# MCORD_AFE_SEC.net
KiCad netlist of a schematic drawn in Altium Designer
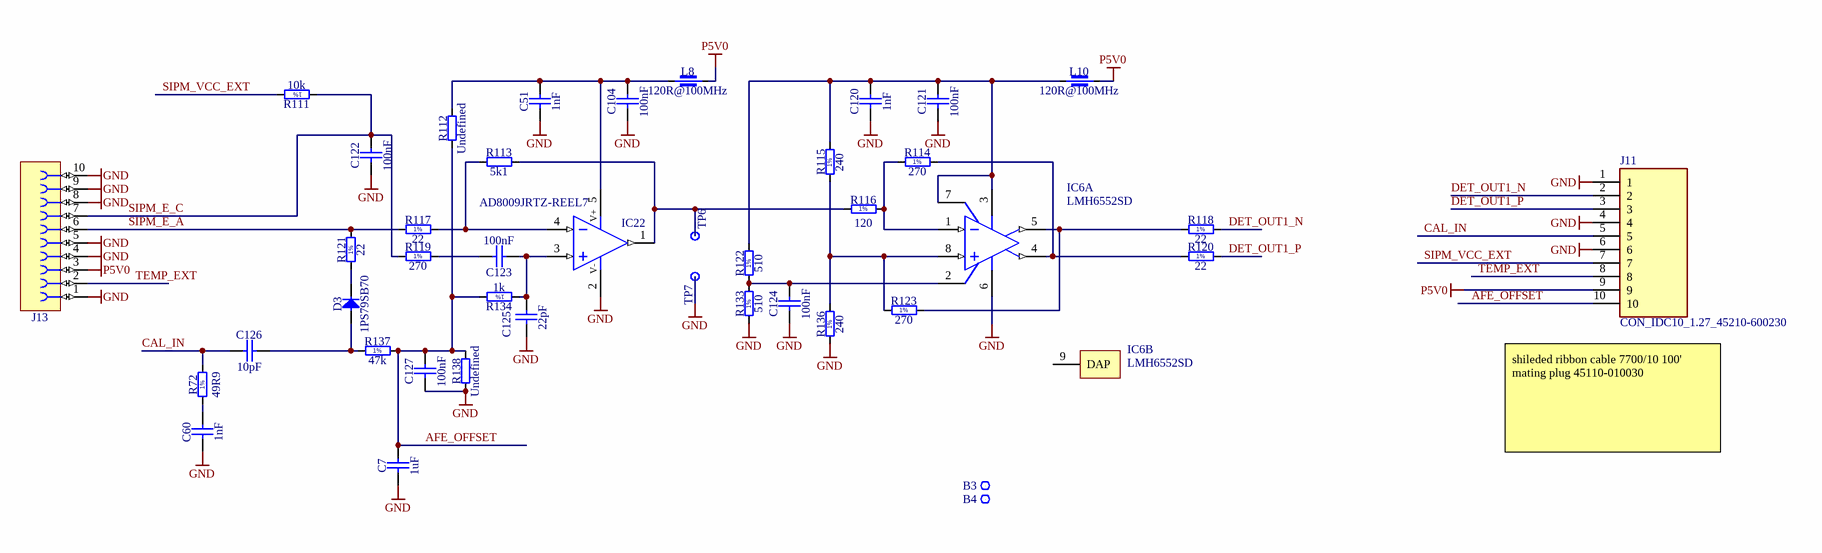
[diagram p0: MCORD_AFE_SEC.SchDoc]

(export (version "E")
  (design (tool "Eeschema 10.0.6"))
  (components
    (comp (ref "B3")
      (value "Plated Hole")
      (footprint "MTG320_550")
      (description "Single Terminal Socket")
      (fields (field (name "PART NUMBER") "PLATED_HOLE3.2_PAD5.5") (field (name "AUTHOR") "CERN DEM JMW"))
      (libsource (lib "Eletro-mechanical") (part "Single Terminal Socket"))
    )
    (comp (ref "B4")
      (value "Plated Hole")
      (footprint "MTG320_550")
      (description "Single Terminal Socket")
      (fields (field (name "PART NUMBER") "PLATED_HOLE3.2_PAD5.5") (field (name "AUTHOR") "CERN DEM JMW"))
      (libsource (lib "Eletro-mechanical") (part "Single Terminal Socket"))
    )
    (comp (ref "C7")
      (value "1uF")
      (footprint "CAPC1608X87N")
      (description "Non-polarised capacitor")
      (fields
        (field (name "PART NUMBER") "CC0603_1UF_16V_10%_X7R")
        (field (name "VOLTAGE") "16V")
        (field (name "AUTHOR") "CERN DEM JLC")
      )
      (libsource (lib "Capacitors") (part "Capacitor - non polarized"))
    )
    (comp (ref "C51")
      (value "1nF")
      (footprint "CAPC1005X55N")
      (description "Non-polarised capacitor")
      (fields
        (field (name "PART NUMBER") "CC0402_1NF_50V_5%_C0G")
        (field (name "VOLTAGE") "50V")
        (field (name "AUTHOR") "CERN DEM BC")
      )
      (libsource (lib "Capacitors") (part "Capacitor - non polarized"))
    )
    (comp (ref "C60")
      (value "1nF")
      (footprint "CAPC1005X55N")
      (description "Non-polarised capacitor")
      (fields
        (field (name "PART NUMBER") "CC0402_1NF_50V_5%_C0G")
        (field (name "VOLTAGE") "50V")
        (field (name "AUTHOR") "CERN DEM BC")
      )
      (libsource (lib "Capacitors") (part "Capacitor - non polarized"))
    )
    (comp (ref "C104")
      (value "100nF")
      (footprint "CAPC1005X55N")
      (description "Non-polarised capacitor")
      (fields
        (field (name "PART NUMBER") "CC0402_100NF_16V_10%_X7R")
        (field (name "VOLTAGE") "16V")
        (field (name "AUTHOR") "CERN DEM JLC")
      )
      (libsource (lib "Capacitors") (part "Capacitor - non polarized"))
    )
    (comp (ref "C120")
      (value "1nF")
      (footprint "CAPC1005X55N")
      (description "Non-polarised capacitor")
      (fields
        (field (name "PART NUMBER") "CC0402_1NF_50V_5%_C0G")
        (field (name "VOLTAGE") "50V")
        (field (name "AUTHOR") "CERN DEM BC")
      )
      (libsource (lib "Capacitors") (part "Capacitor - non polarized"))
    )
    (comp (ref "C121")
      (value "100nF")
      (footprint "CAPC1005X55N")
      (description "Non-polarised capacitor")
      (fields
        (field (name "PART NUMBER") "CC0402_100NF_16V_10%_X7R")
        (field (name "VOLTAGE") "16V")
        (field (name "AUTHOR") "CERN DEM JLC")
      )
      (libsource (lib "Capacitors") (part "Capacitor - non polarized"))
    )
    (comp (ref "C122")
      (value "100nF")
      (footprint "CAPC1608X90N")
      (description "Non-polarised capacitor")
      (fields
        (field (name "PART NUMBER") "CC0603_100NF_100V_10%_X7R")
        (field (name "VOLTAGE") "100V")
        (field (name "AUTHOR") "CERN DEM JLC")
      )
      (libsource (lib "Capacitors") (part "Capacitor - non polarized"))
    )
    (comp (ref "C123")
      (value "100nF")
      (footprint "CAPC1608X90N")
      (description "Non-polarised capacitor")
      (fields
        (field (name "PART NUMBER") "CC0603_100NF_100V_10%_X7R")
        (field (name "VOLTAGE") "100V")
        (field (name "AUTHOR") "CERN DEM JLC")
      )
      (libsource (lib "Capacitors") (part "Capacitor - non polarized"))
    )
    (comp (ref "C124")
      (value "100nF")
      (footprint "CAPC1005X55N")
      (description "Non-polarised capacitor")
      (fields
        (field (name "PART NUMBER") "CC0402_100NF_16V_10%_X7R")
        (field (name "VOLTAGE") "16V")
        (field (name "AUTHOR") "CERN DEM JLC")
      )
      (libsource (lib "Capacitors") (part "Capacitor - non polarized"))
    )
    (comp (ref "C125")
      (value "22pF")
      (footprint "CAPC1005X55N")
      (description "Non-polarised capacitor")
      (fields
        (field (name "PART NUMBER") "CC0402_22PF_50V_5%_C0G")
        (field (name "VOLTAGE") "50V")
        (field (name "AUTHOR") "CERN DEM JLC")
      )
      (libsource (lib "Capacitors") (part "Capacitor - non polarized"))
    )
    (comp (ref "C126")
      (value "10pF")
      (footprint "CAPC1608X87N")
      (description "Non-polarised capacitor")
      (fields
        (field (name "PART NUMBER") "CC0603_10PF_50V_5%_NP0")
        (field (name "VOLTAGE") "50V")
        (field (name "AUTHOR") "CERN DEM JLC")
      )
      (libsource (lib "Capacitors") (part "Capacitor - non polarized"))
    )
    (comp (ref "C127")
      (value "100nF")
      (footprint "CAPC1005X55N")
      (description "Non-polarised capacitor")
      (fields
        (field (name "PART NUMBER") "CC0402_100NF_16V_10%_X7R")
        (field (name "VOLTAGE") "16V")
        (field (name "AUTHOR") "CERN DEM JLC")
      )
      (libsource (lib "Capacitors") (part "Capacitor - non polarized"))
    )
    (comp (ref "D3")
      (value "1PS79SB70")
      (footprint "SODFL1608X65N")
      (description "Diode")
      (fields (field (name "VOLTAGE") "70V") (field (name "POWER") "70mA") (field (name "AUTHOR") "GK"))
      (libsource (lib "Diodes") (part "D_1PS79SB70"))
    )
    (comp (ref "IC6")
      (value "LMH6552SD")
      (footprint "SDA08C")
      (description "1.5 GHz Fully Differential Amplifier, 8-pin LLP")
      (fields (field (name "MANUFACTURER") "National Semiconductor"))
      (libsource (lib "Altium Content Vault") (part "AMP-DIFA-LMH6552-9"))
    )
    (comp (ref "IC22")
      (value "AD8009JRTZ-REEL7")
      (footprint "SOT95P280X145-5N")
      (description "Operational Amplifier")
      (fields (field (name "MANUFACTURER") "ANALOG DEVICES") (field (name "AUTHOR") "CERN DEM JLC"))
      (libsource (lib "ICs And Semiconductors") (part "Operational Amplifier Type7"))
    )
    (comp (ref "J11")
      (value "CON_IDC10_1.27_45210-600230")
      (footprint "SamacSys:SHDR10W38P127_2X5_1069X594X747P")
      (description "Connector")
      (fields
        (field (name "MANUFACTURER_PART_NUMBER") "45210-600230")
        (field (name "MOUSER PART NUMBER") "517-45210-600230")
      )
      (libsource (lib "LIBRARY_SCH") (part "CON_IDC10_1.27_45210-600230"))
    )
    (comp (ref "J13")
      (value "FFC/FPC")
      (footprint "MOLEX_52745-1097")
      (description "Connector 10 Female")
      (fields
        (field (name "PART NUMBER") "MOLEX_52745-1097")
        (field (name "MANUFACTURER") "MOLEX")
        (field (name "AUTHOR") "CERN DEM JLC")
      )
      (libsource (lib "Connectors") (part "Connector 10 Female"))
    )
    (comp (ref "L8")
      (value "120R@100MHz")
      (footprint "INDC1005X55N")
      (fields
        (field (name "PART NUMBER") "IND0402_MURATA_BLM15PX121SN1D")
        (field (name "POWER") "2A")
        (field (name "TOLERANCE") "±25%")
        (field (name "AUTHOR") "CERN DEM JMW")
      )
      (libsource (lib "Inductors & Transformers") (part "Ferrite Bead"))
    )
    (comp (ref "L10")
      (value "120R@100MHz")
      (footprint "INDC1005X55N")
      (fields
        (field (name "PART NUMBER") "IND0402_MURATA_BLM15PX121SN1D")
        (field (name "POWER") "2A")
        (field (name "TOLERANCE") "±25%")
        (field (name "AUTHOR") "CERN DEM JMW")
      )
      (libsource (lib "Inductors & Transformers") (part "Ferrite Bead"))
    )
    (comp (ref "R72")
      (value "49R9")
      (footprint "RESC1005X40N")
      (description "Resistor - 1%")
      (fields
        (field (name "PART NUMBER") "R0402_49R9_1%_0.0625W_100PPM")
        (field (name "POWER") "0.0625W")
        (field (name "AUTHOR") "CERN DEM JLC")
      )
      (libsource (lib "Resistors") (part "Resistor - 1%"))
    )
    (comp (ref "R111")
      (value "10k")
      (footprint "RESC1005X40N")
      (description "Resistor - 1%")
      (fields
        (field (name "PART NUMBER") "R0402_10K_1%_0.0625W_100PPM")
        (field (name "POWER") "0.0625W")
        (field (name "AUTHOR") "CERN DEM JLC")
      )
      (libsource (lib "Resistors") (part "Resistor - 1%"))
    )
    (comp (ref "R112")
      (value "Undefined")
      (footprint "RESC1005X40N")
      (description "Resistor")
      (fields (field (name "PART NUMBER") "R0402_NO-VALUE") (field (name "AUTHOR") "CERN DEM JLC"))
      (libsource (lib "Resistors") (part "Resistor"))
    )
    (comp (ref "R113")
      (value "5k1")
      (footprint "RESC1005X40N")
      (description "Resistor - 1%")
      (fields
        (field (name "PART NUMBER") "R0402_5K1_1%_0.0625W_100PPM")
        (field (name "POWER") "0.0625W")
        (field (name "AUTHOR") "CERN DEM JLC")
      )
      (libsource (lib "Resistors") (part "Resistor - 1%"))
    )
    (comp (ref "R114")
      (value "270")
      (footprint "RESC1005X40N")
      (description "Resistor - 1%")
      (fields
        (field (name "PART NUMBER") "R0402_270R_1%_0.0625W_100PPM")
        (field (name "POWER") "0.0625W")
        (field (name "AUTHOR") "CERN DEM JLC")
      )
      (libsource (lib "Resistors") (part "Resistor - 1%"))
    )
    (comp (ref "R115")
      (value "240")
      (footprint "RESC1005X40N")
      (description "Resistor - 1%")
      (fields
        (field (name "PART NUMBER") "R0402_240R_1%_0.0625W_100PPM")
        (field (name "POWER") "0.0625W")
        (field (name "AUTHOR") "CERN DEM JLC")
      )
      (libsource (lib "Resistors") (part "Resistor - 1%"))
    )
    (comp (ref "R116")
      (value "120")
      (footprint "RESC1005X40N")
      (description "Resistor - 1%")
      (fields
        (field (name "PART NUMBER") "R0402_120R_1%_0.0625W_100PPM")
        (field (name "POWER") "0.0625W")
        (field (name "AUTHOR") "CERN DEM JLC")
      )
      (libsource (lib "Resistors") (part "Resistor - 1%"))
    )
    (comp (ref "R117")
      (value "22")
      (footprint "RESC1608X55N")
      (description "Resistor - 1%")
      (fields
        (field (name "PART NUMBER") "R0603_22R_1%_0.1W_100PPM")
        (field (name "POWER") "0.1W")
        (field (name "AUTHOR") "CERN DEM JLC")
      )
      (libsource (lib "") (part "Resistor - 1%_1"))
    )
    (comp (ref "R118")
      (value "22")
      (footprint "RESC1608X55N")
      (description "Resistor - 1%")
      (fields
        (field (name "PART NUMBER") "R0603_22R_1%_0.1W_100PPM")
        (field (name "POWER") "0.1W")
        (field (name "AUTHOR") "CERN DEM JLC")
      )
      (libsource (lib "") (part "Resistor - 1%_1"))
    )
    (comp (ref "R119")
      (value "270")
      (footprint "RESC1005X40N")
      (description "Resistor - 1%")
      (fields
        (field (name "PART NUMBER") "R0402_270R_1%_0.0625W_100PPM")
        (field (name "POWER") "0.0625W")
        (field (name "AUTHOR") "CERN DEM JLC")
      )
      (libsource (lib "Resistors") (part "Resistor - 1%"))
    )
    (comp (ref "R120")
      (value "22")
      (footprint "RESC1608X55N")
      (description "Resistor - 1%")
      (fields
        (field (name "PART NUMBER") "R0603_22R_1%_0.1W_100PPM")
        (field (name "POWER") "0.1W")
        (field (name "AUTHOR") "CERN DEM JLC")
      )
      (libsource (lib "") (part "Resistor - 1%_1"))
    )
    (comp (ref "R121")
      (value "22")
      (footprint "RESC1608X55N")
      (description "Resistor - 1%")
      (fields
        (field (name "PART NUMBER") "R0603_22R_1%_0.1W_100PPM")
        (field (name "POWER") "0.1W")
        (field (name "AUTHOR") "CERN DEM JLC")
      )
      (libsource (lib "") (part "Resistor - 1%_1"))
    )
    (comp (ref "R122")
      (value "510")
      (footprint "RESC1005X40N")
      (description "Resistor - 1%")
      (fields
        (field (name "PART NUMBER") "R0402_510R_1%_0.0625W_100PPM")
        (field (name "POWER") "0.0625W")
        (field (name "AUTHOR") "CERN DEM JLC")
      )
      (libsource (lib "Resistors") (part "Resistor - 1%"))
    )
    (comp (ref "R123")
      (value "270")
      (footprint "RESC1005X40N")
      (description "Resistor - 1%")
      (fields
        (field (name "PART NUMBER") "R0402_270R_1%_0.0625W_100PPM")
        (field (name "POWER") "0.0625W")
        (field (name "AUTHOR") "CERN DEM JLC")
      )
      (libsource (lib "Resistors") (part "Resistor - 1%"))
    )
    (comp (ref "R133")
      (value "510")
      (footprint "RESC1005X40N")
      (description "Resistor - 1%")
      (fields
        (field (name "PART NUMBER") "R0402_510R_1%_0.0625W_100PPM")
        (field (name "POWER") "0.0625W")
        (field (name "AUTHOR") "CERN DEM JLC")
      )
      (libsource (lib "Resistors") (part "Resistor - 1%"))
    )
    (comp (ref "R134")
      (value "1k")
      (footprint "RESC1005X40N")
      (description "Resistor - 1%")
      (fields
        (field (name "PART NUMBER") "R0402_1K_1%_0.0625W_100PPM")
        (field (name "POWER") "0.0625W")
        (field (name "AUTHOR") "CERN DEM JLC")
      )
      (libsource (lib "Resistors") (part "Resistor - 1%"))
    )
    (comp (ref "R136")
      (value "240")
      (footprint "RESC1005X40N")
      (description "Resistor - 1%")
      (fields
        (field (name "PART NUMBER") "R0402_240R_1%_0.0625W_100PPM")
        (field (name "POWER") "0.0625W")
        (field (name "AUTHOR") "CERN DEM JLC")
      )
      (libsource (lib "Resistors") (part "Resistor - 1%"))
    )
    (comp (ref "R137")
      (value "47k")
      (footprint "RESC1005X40N")
      (description "Resistor - 1%")
      (fields
        (field (name "PART NUMBER") "R0402_47K_1%_0.0625W_100PPM")
        (field (name "POWER") "0.0625W")
        (field (name "AUTHOR") "CERN DEM JLC")
      )
      (libsource (lib "Resistors") (part "Resistor - 1%"))
    )
    (comp (ref "R138")
      (value "Undefined")
      (footprint "RESC1005X40N")
      (description "Resistor")
      (fields (field (name "PART NUMBER") "R0402_NO-VALUE") (field (name "AUTHOR") "CERN DEM JLC"))
      (libsource (lib "Resistors") (part "Resistor"))
    )
    (comp (ref "TP6")
      (value "Test Point")
      (footprint "TPS127")
      (fields (field (name "PART NUMBER") "SMD_PAD_1.27X1.27MM") (field (name "AUTHOR") "CERN DEM JLC"))
      (libsource (lib "Eletro-mechanical") (part "Test Point"))
    )
    (comp (ref "TP7")
      (value "Test Point")
      (footprint "TPS127")
      (fields (field (name "PART NUMBER") "SMD_PAD_1.27X1.27MM") (field (name "AUTHOR") "CERN DEM JLC"))
      (libsource (lib "Eletro-mechanical") (part "Test Point"))
    )
  )
  (nets
    (net (code "1") (name "/AFE_OFFSET") (class "Default")
      (node (ref "C127") (pin "2") (pinfunction "2_2") (pintype "passive"))
      (node (ref "C7") (pin "2") (pinfunction "2_2") (pintype "passive"))
      (node (ref "J11") (pin "10") (pinfunction "10_10") (pintype "passive"))
      (node (ref "R112") (pin "1") (pinfunction "1_1") (pintype "passive"))
      (node (ref "R134") (pin "2") (pinfunction "2_2") (pintype "passive"))
      (node (ref "R137") (pin "2") (pinfunction "2_2") (pintype "passive"))
      (node (ref "R138") (pin "2") (pinfunction "2_2") (pintype "passive"))
    )
    (net (code "2") (name "/CAL_IN") (class "Default")
      (node (ref "C126") (pin "1") (pinfunction "1_1") (pintype "passive"))
      (node (ref "J11") (pin "5") (pinfunction "5_5") (pintype "passive"))
      (node (ref "R72") (pin "2") (pinfunction "2_2") (pintype "passive"))
    )
    (net (code "3") (name "/DET_OUT1_N") (class "Default")
      (node (ref "J11") (pin "2") (pinfunction "2_2") (pintype "passive"))
      (node (ref "R118") (pin "2") (pinfunction "2_2") (pintype "passive"))
    )
    (net (code "4") (name "/DET_OUT1_P") (class "Default")
      (node (ref "J11") (pin "3") (pinfunction "3_3") (pintype "passive"))
      (node (ref "R120") (pin "2") (pinfunction "2_2") (pintype "passive"))
    )
    (net (code "5") (name "/SIPM_E_A") (class "Default")
      (node (ref "J13") (pin "6") (pinfunction "6_6") (pintype "bidirectional"))
      (node (ref "R117") (pin "1") (pinfunction "1_1") (pintype "passive"))
      (node (ref "R121") (pin "2") (pinfunction "2_2") (pintype "passive"))
    )
    (net (code "6") (name "/SIPM_E_C") (class "Default")
      (node (ref "C122") (pin "2") (pinfunction "2_2") (pintype "passive"))
      (node (ref "J13") (pin "7") (pinfunction "7_7") (pintype "bidirectional"))
      (node (ref "R111") (pin "1") (pinfunction "1_1") (pintype "passive"))
      (node (ref "R119") (pin "1") (pinfunction "1_1") (pintype "passive"))
    )
    (net (code "7") (name "/SIPM_VCC_EXT") (class "Default")
      (node (ref "J11") (pin "7") (pinfunction "7_7") (pintype "passive"))
      (node (ref "R111") (pin "2") (pinfunction "2_2") (pintype "passive"))
    )
    (net (code "8") (name "/TEMP_EXT") (class "Default")
      (node (ref "J11") (pin "8") (pinfunction "8_8") (pintype "passive"))
      (node (ref "J13") (pin "2") (pinfunction "2_2") (pintype "bidirectional"))
    )
    (net (code "9") (name "GND") (class "Default")
      (node (ref "C104") (pin "1") (pinfunction "1_1") (pintype "passive"))
      (node (ref "C120") (pin "1") (pinfunction "1_1") (pintype "passive"))
      (node (ref "C121") (pin "1") (pinfunction "1_1") (pintype "passive"))
      (node (ref "C122") (pin "1") (pinfunction "1_1") (pintype "passive"))
      (node (ref "C124") (pin "1") (pinfunction "1_1") (pintype "passive"))
      (node (ref "C125") (pin "1") (pinfunction "1_1") (pintype "passive"))
      (node (ref "C127") (pin "1") (pinfunction "1_1") (pintype "passive"))
      (node (ref "C51") (pin "1") (pinfunction "1_1") (pintype "passive"))
      (node (ref "C60") (pin "1") (pinfunction "1_1") (pintype "passive"))
      (node (ref "C7") (pin "1") (pinfunction "1_1") (pintype "passive"))
      (node (ref "IC22") (pin "2") (pinfunction "V-_2") (pintype "power_in"))
      (node (ref "IC6") (pin "6") (pinfunction "V-_6") (pintype "power_in"))
      (node (ref "J11") (pin "1") (pinfunction "1_1") (pintype "passive"))
      (node (ref "J11") (pin "4") (pinfunction "4_4") (pintype "passive"))
      (node (ref "J11") (pin "6") (pinfunction "6_6") (pintype "passive"))
      (node (ref "J13") (pin "1") (pinfunction "1_1") (pintype "bidirectional"))
      (node (ref "J13") (pin "10") (pinfunction "10_10") (pintype "bidirectional"))
      (node (ref "J13") (pin "4") (pinfunction "4_4") (pintype "bidirectional"))
      (node (ref "J13") (pin "5") (pinfunction "5_5") (pintype "bidirectional"))
      (node (ref "J13") (pin "8") (pinfunction "8_8") (pintype "bidirectional"))
      (node (ref "J13") (pin "9") (pinfunction "9_9") (pintype "bidirectional"))
      (node (ref "R133") (pin "1") (pinfunction "1_1") (pintype "passive"))
      (node (ref "R136") (pin "1") (pinfunction "1_1") (pintype "passive"))
      (node (ref "R138") (pin "1") (pinfunction "1_1") (pintype "passive"))
      (node (ref "TP7") (pin "1") (pinfunction "1_1") (pintype "bidirectional"))
    )
    (net (code "10") (name "Net-(C60-Pad2)") (class "Default")
      (node (ref "C60") (pin "2") (pinfunction "2_2") (pintype "passive"))
      (node (ref "R72") (pin "1") (pinfunction "1_1") (pintype "passive"))
    )
    (net (code "11") (name "Net-(C123-Pad2)") (class "Default")
      (node (ref "C123") (pin "2") (pinfunction "2_2") (pintype "passive"))
      (node (ref "R119") (pin "2") (pinfunction "2_2") (pintype "passive"))
    )
    (net (code "12") (name "Net-(D3-A)") (class "Default")
      (node (ref "C126") (pin "2") (pinfunction "2_2") (pintype "passive"))
      (node (ref "D3") (pin "2") (pinfunction "A_2") (pintype "passive"))
      (node (ref "R137") (pin "1") (pinfunction "1_1") (pintype "passive"))
    )
    (net (code "13") (name "Net-(D3-C)") (class "Default")
      (node (ref "D3") (pin "1") (pinfunction "C_1") (pintype "passive"))
      (node (ref "R121") (pin "1") (pinfunction "1_1") (pintype "passive"))
    )
    (net (code "14") (name "Net-(IC6A-EN)") (class "Default")
      (node (ref "C120") (pin "2") (pinfunction "2_2") (pintype "passive"))
      (node (ref "C121") (pin "2") (pinfunction "2_2") (pintype "passive"))
      (node (ref "IC6") (pin "3") (pinfunction "V+_3") (pintype "power_in"))
      (node (ref "IC6") (pin "7") (pinfunction "EN_7") (pintype "passive"))
      (node (ref "L10") (pin "1") (pinfunction "1_1") (pintype "passive"))
      (node (ref "R115") (pin "2") (pinfunction "2_2") (pintype "passive"))
      (node (ref "R122") (pin "2") (pinfunction "2_2") (pintype "passive"))
    )
    (net (code "15") (name "Net-(IC6A-IN+)") (class "Default")
      (node (ref "IC6") (pin "8") (pinfunction "IN+_8") (pintype "input"))
      (node (ref "R115") (pin "1") (pinfunction "1_1") (pintype "passive"))
      (node (ref "R123") (pin "1") (pinfunction "1_1") (pintype "passive"))
      (node (ref "R136") (pin "2") (pinfunction "2_2") (pintype "passive"))
    )
    (net (code "16") (name "Net-(IC6A-IN-)") (class "Default")
      (node (ref "IC6") (pin "1") (pinfunction "IN-_1") (pintype "input"))
      (node (ref "R114") (pin "1") (pinfunction "1_1") (pintype "passive"))
      (node (ref "R116") (pin "2") (pinfunction "2_2") (pintype "passive"))
    )
    (net (code "17") (name "Net-(IC6A-OUT+)") (class "Default")
      (node (ref "IC6") (pin "4") (pinfunction "OUT+_4") (pintype "output"))
      (node (ref "R114") (pin "2") (pinfunction "2_2") (pintype "passive"))
      (node (ref "R120") (pin "1") (pinfunction "1_1") (pintype "passive"))
    )
    (net (code "18") (name "Net-(IC6A-OUT-)") (class "Default")
      (node (ref "IC6") (pin "5") (pinfunction "OUT-_5") (pintype "output"))
      (node (ref "R118") (pin "1") (pinfunction "1_1") (pintype "passive"))
      (node (ref "R123") (pin "2") (pinfunction "2_2") (pintype "passive"))
    )
    (net (code "19") (name "Net-(IC6A-VCM)") (class "Default")
      (node (ref "C124") (pin "2") (pinfunction "2_2") (pintype "passive"))
      (node (ref "IC6") (pin "2") (pinfunction "VCM_2") (pintype "passive"))
      (node (ref "R122") (pin "1") (pinfunction "1_1") (pintype "passive"))
      (node (ref "R133") (pin "2") (pinfunction "2_2") (pintype "passive"))
    )
    (net (code "20") (name "Net-(IC22-IN+)") (class "Default")
      (node (ref "C123") (pin "1") (pinfunction "1_1") (pintype "passive"))
      (node (ref "C125") (pin "2") (pinfunction "2_2") (pintype "passive"))
      (node (ref "IC22") (pin "3") (pinfunction "IN+_3") (pintype "input"))
      (node (ref "R134") (pin "1") (pinfunction "1_1") (pintype "passive"))
    )
    (net (code "21") (name "Net-(IC22-IN-)") (class "Default")
      (node (ref "IC22") (pin "4") (pinfunction "IN-_4") (pintype "input"))
      (node (ref "R113") (pin "1") (pinfunction "1_1") (pintype "passive"))
      (node (ref "R117") (pin "2") (pinfunction "2_2") (pintype "passive"))
    )
    (net (code "22") (name "Net-(IC22-OUT)") (class "Default")
      (node (ref "IC22") (pin "1") (pinfunction "OUT_1") (pintype "output"))
      (node (ref "R113") (pin "2") (pinfunction "2_2") (pintype "passive"))
      (node (ref "R116") (pin "1") (pinfunction "1_1") (pintype "passive"))
      (node (ref "TP6") (pin "1") (pinfunction "1_1") (pintype "bidirectional"))
    )
    (net (code "23") (name "Net-(IC22-V+)") (class "Default")
      (node (ref "C104") (pin "2") (pinfunction "2_2") (pintype "passive"))
      (node (ref "C51") (pin "2") (pinfunction "2_2") (pintype "passive"))
      (node (ref "IC22") (pin "5") (pinfunction "V+_5") (pintype "power_in"))
      (node (ref "L8") (pin "1") (pinfunction "1_1") (pintype "passive"))
      (node (ref "R112") (pin "2") (pinfunction "2_2") (pintype "passive"))
    )
    (net (code "24") (name "P5V0") (class "Default")
      (node (ref "J11") (pin "9") (pinfunction "9_9") (pintype "passive"))
      (node (ref "J13") (pin "3") (pinfunction "3_3") (pintype "bidirectional"))
      (node (ref "L10") (pin "2") (pinfunction "2_2") (pintype "passive"))
      (node (ref "L8") (pin "2") (pinfunction "2_2") (pintype "passive"))
    )
    (net (code "25") (name "unconnected-(B3-Pad1)") (class "Default")
      (node (ref "B3") (pin "1") (pinfunction "1_1") (pintype "bidirectional"))
    )
    (net (code "26") (name "unconnected-(B4-Pad1)") (class "Default")
      (node (ref "B4") (pin "1") (pinfunction "1_1") (pintype "bidirectional"))
    )
    (net (code "27") (name "unconnected-(IC6B-DAP-Pad9)") (class "Default")
      (node (ref "IC6") (pin "9") (pinfunction "DAP_9") (pintype "passive"))
    )
  )
)
